# nestWidget.net
KiCad netlist of a schematic drawn in EAGLE
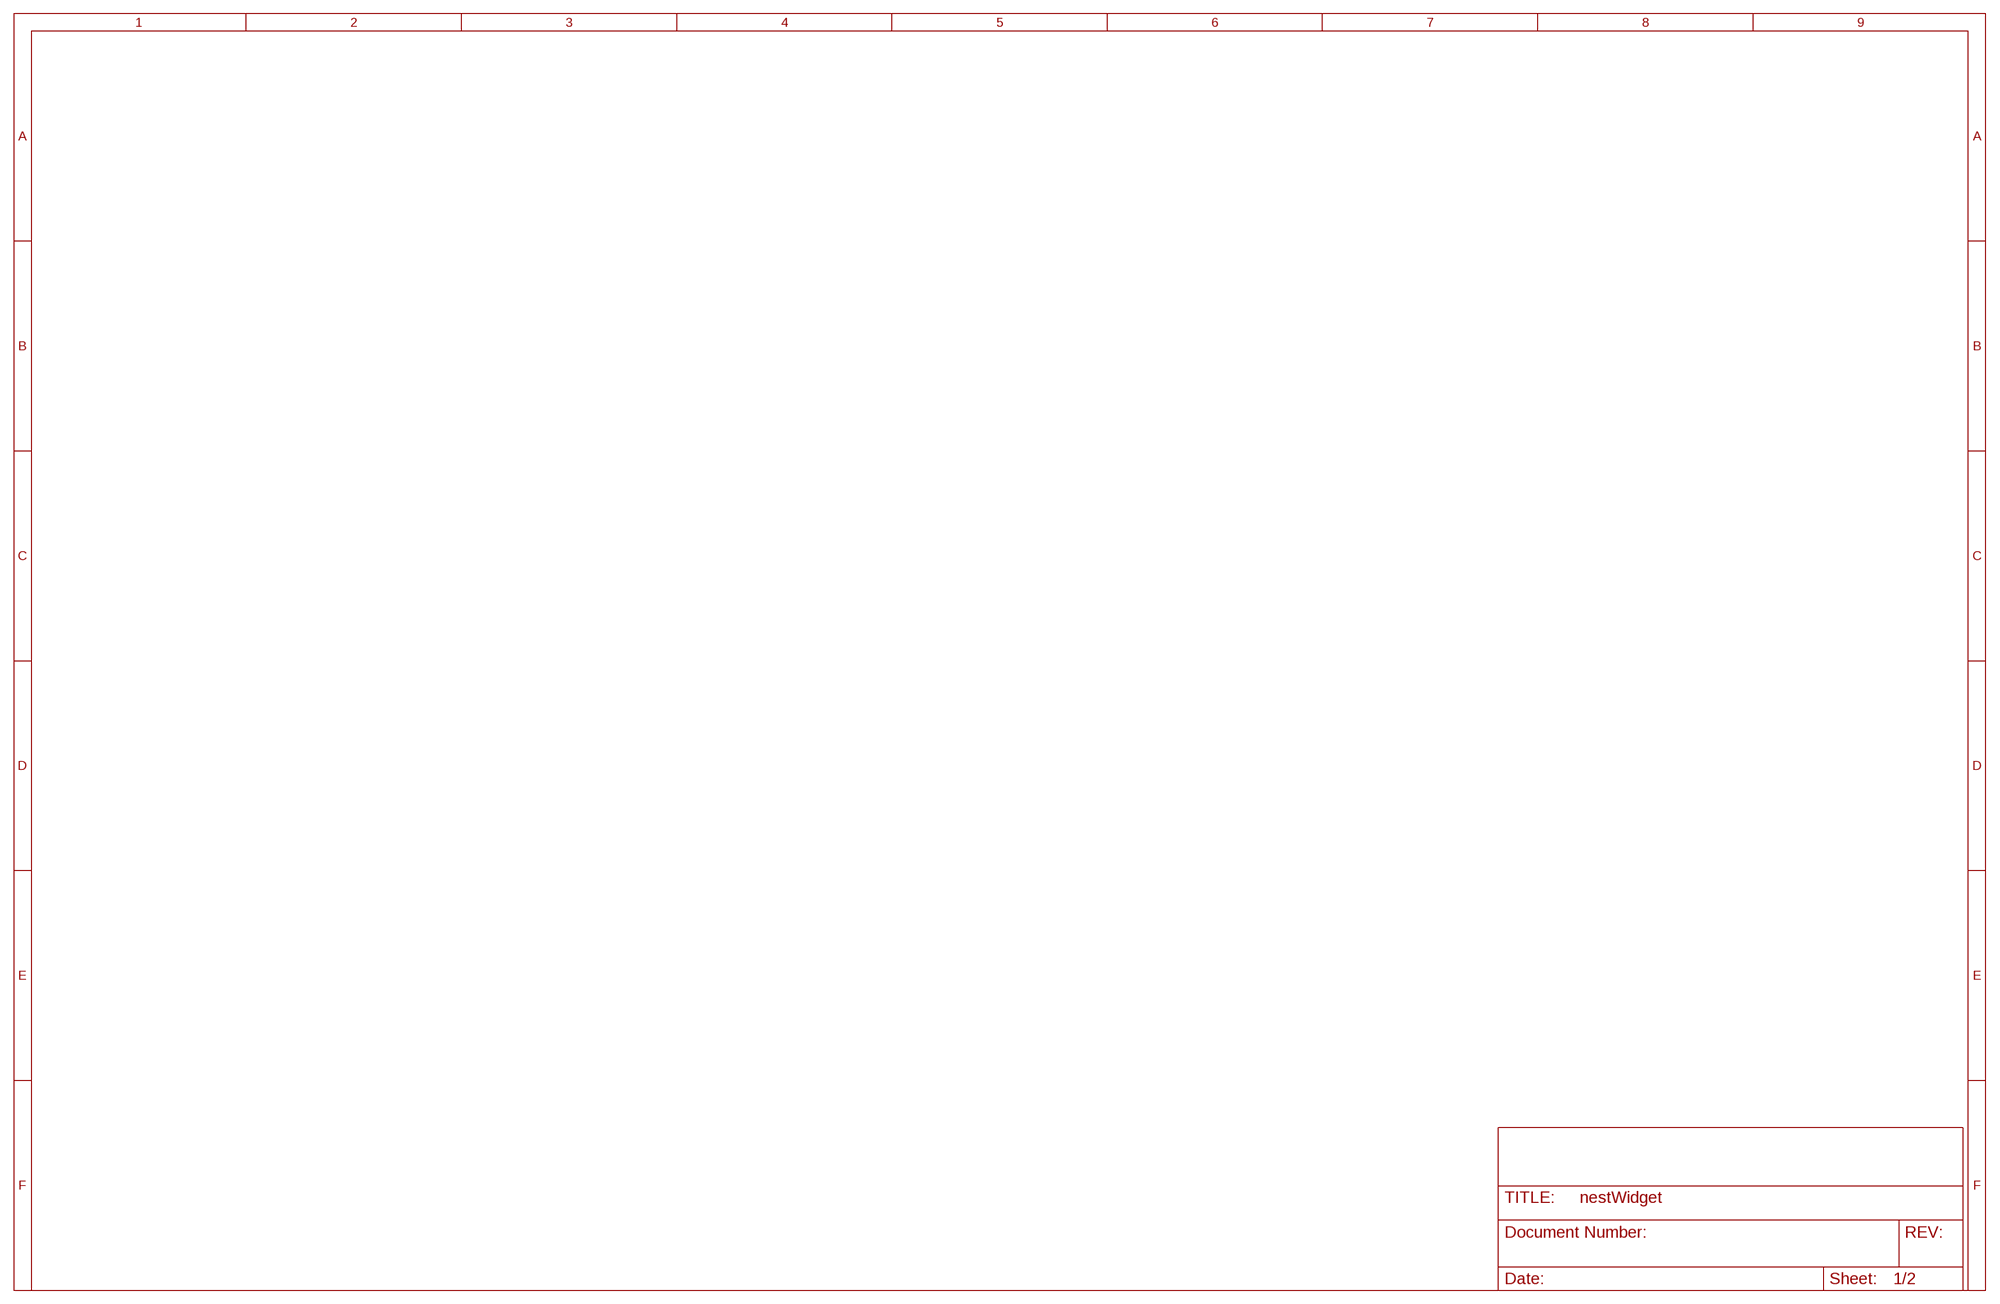
[diagram p0: schematic, sheet 1]
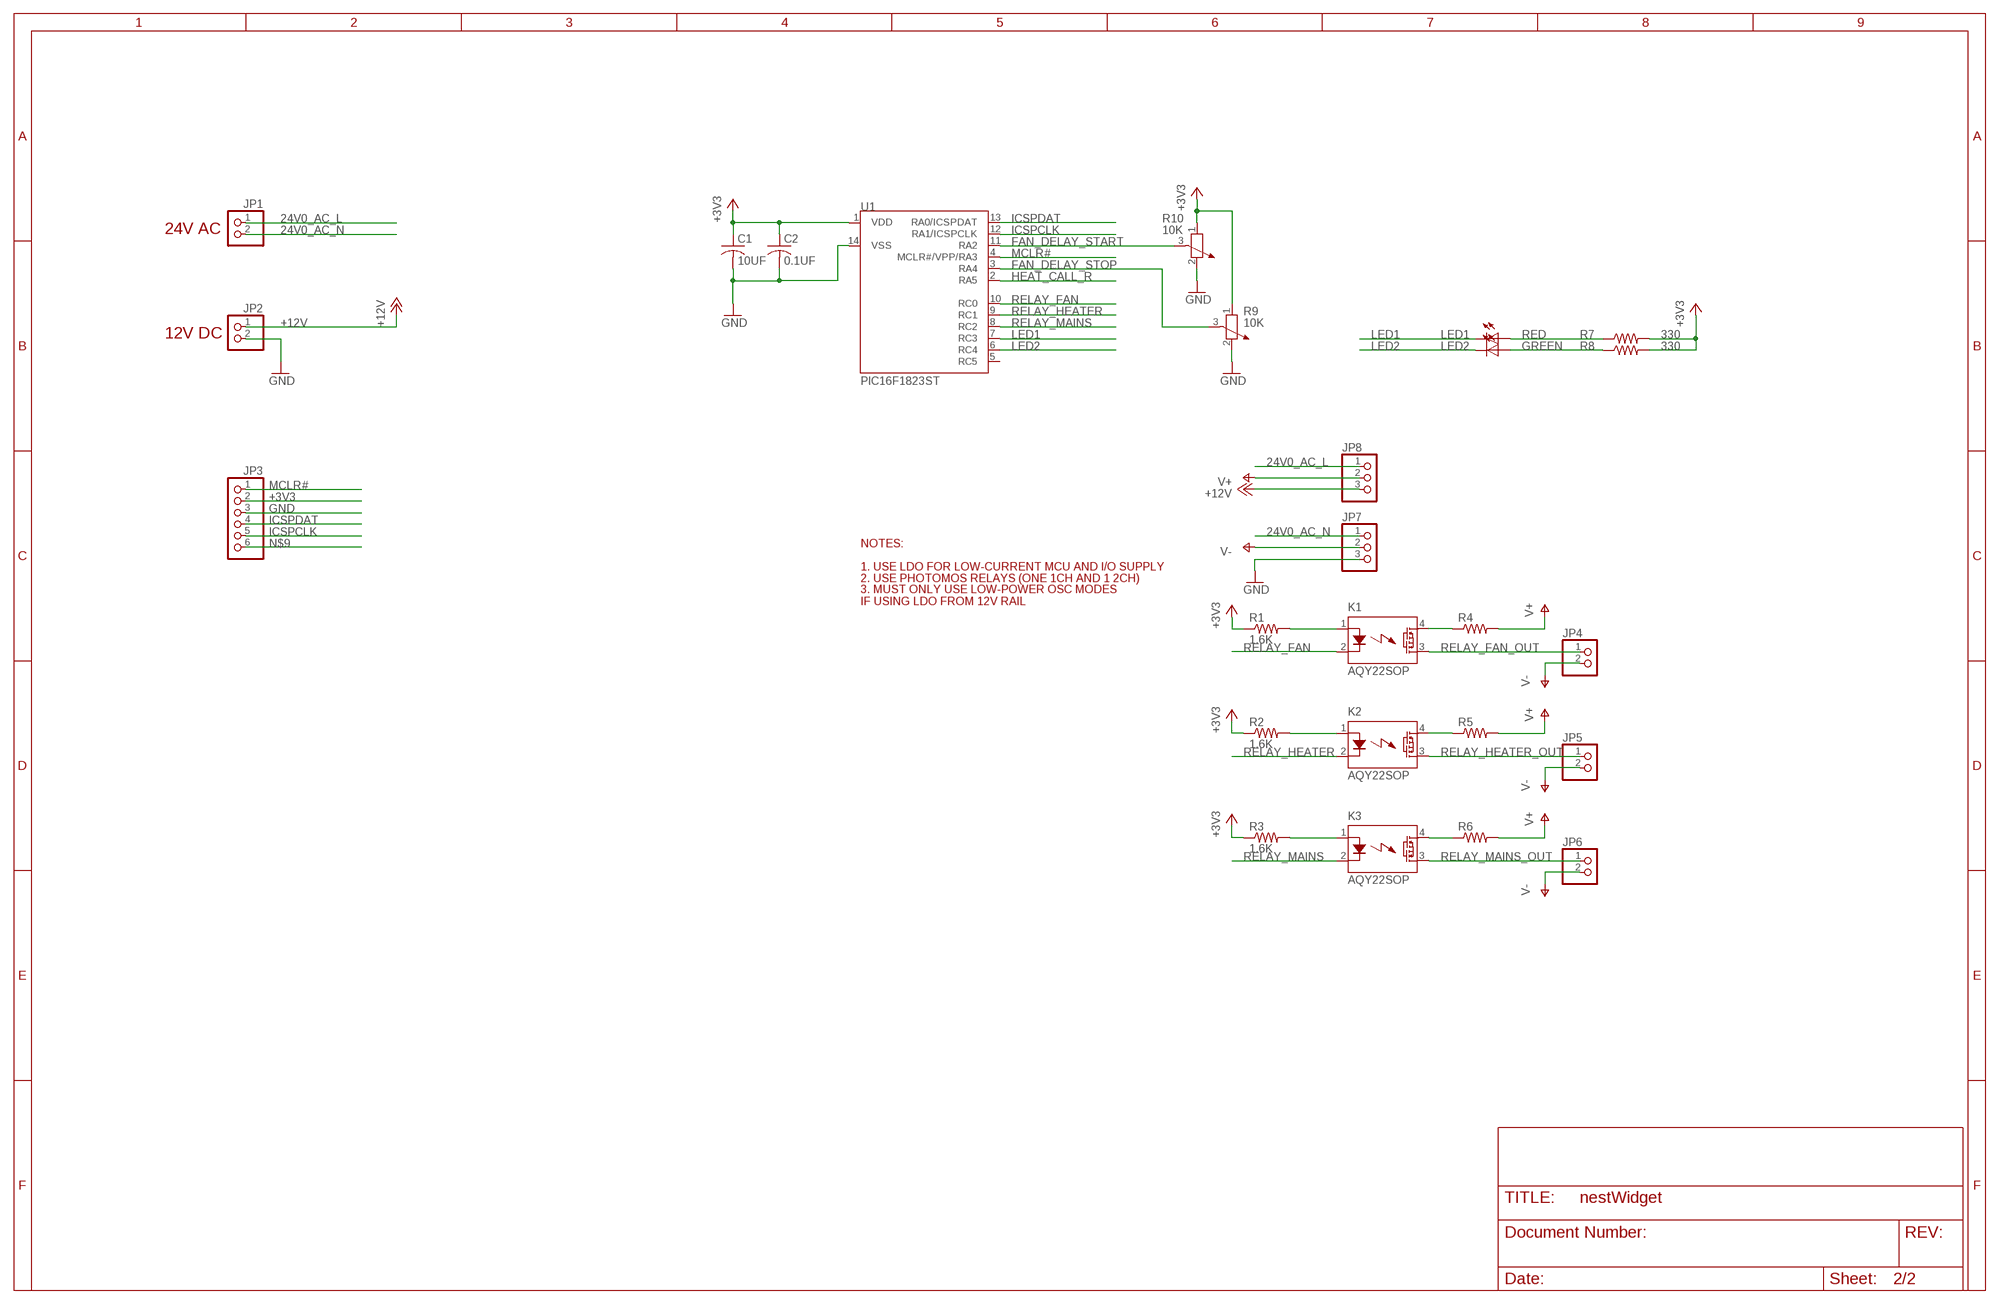
[diagram p1: schematic, sheet 2]

(export (version "E")
  (design (tool "Eeschema 10.0.6"))
  (components
    (comp (ref "C1")
      (value "10UF")
      (footprint "eagle-import:C0603")
      (libsource (lib "eagle-import") (part "C-USC0603"))
    )
    (comp (ref "C2")
      (value "0.1UF")
      (footprint "eagle-import:C0603")
      (libsource (lib "eagle-import") (part "C-USC0603"))
    )
    (comp (ref "JP1")
      (value "PINHD-1X2")
      (footprint "eagle-import:1X02")
      (libsource (lib "eagle-import") (part "PINHD-1X2"))
    )
    (comp (ref "JP2")
      (value "PINHD-1X2")
      (footprint "eagle-import:1X02")
      (libsource (lib "eagle-import") (part "PINHD-1X2"))
    )
    (comp (ref "JP3")
      (value "PINHD-1X6")
      (footprint "eagle-import:1X06")
      (libsource (lib "eagle-import") (part "PINHD-1X6"))
    )
    (comp (ref "JP4")
      (value "PINHD-1X2")
      (footprint "eagle-import:1X02")
      (libsource (lib "eagle-import") (part "PINHD-1X2"))
    )
    (comp (ref "JP5")
      (value "PINHD-1X2")
      (footprint "eagle-import:1X02")
      (libsource (lib "eagle-import") (part "PINHD-1X2"))
    )
    (comp (ref "JP6")
      (value "PINHD-1X2")
      (footprint "eagle-import:1X02")
      (libsource (lib "eagle-import") (part "PINHD-1X2"))
    )
    (comp (ref "JP7")
      (value "PINHD-1X3")
      (footprint "eagle-import:1X03")
      (libsource (lib "eagle-import") (part "PINHD-1X3"))
    )
    (comp (ref "JP8")
      (value "PINHD-1X3")
      (footprint "eagle-import:1X03")
      (libsource (lib "eagle-import") (part "PINHD-1X3"))
    )
    (comp (ref "K1")
      (value "AQY22SOP")
      (footprint "eagle-import:SOP04")
      (libsource (lib "eagle-import") (part "AQYSOP22"))
    )
    (comp (ref "K2")
      (value "AQY22SOP")
      (footprint "eagle-import:SOP04")
      (libsource (lib "eagle-import") (part "AQYSOP22"))
    )
    (comp (ref "K3")
      (value "AQY22SOP")
      (footprint "eagle-import:SOP04")
      (libsource (lib "eagle-import") (part "AQYSOP22"))
    )
    (comp (ref "LED1")
      (value "RED")
      (footprint "eagle-import:CHIPLED_0603")
      (libsource (lib "eagle-import") (part "LEDCHIPLED_0603"))
    )
    (comp (ref "LED2")
      (value "GREEN")
      (footprint "eagle-import:CHIPLED_0603")
      (libsource (lib "eagle-import") (part "LEDCHIPLED_0603"))
    )
    (comp (ref "R1")
      (value "1.6K")
      (footprint "eagle-import:R0603")
      (libsource (lib "eagle-import") (part "R-US_R0603"))
    )
    (comp (ref "R2")
      (value "1.6K")
      (footprint "eagle-import:R0603")
      (libsource (lib "eagle-import") (part "R-US_R0603"))
    )
    (comp (ref "R3")
      (value "1.6K")
      (footprint "eagle-import:R0603")
      (libsource (lib "eagle-import") (part "R-US_R0603"))
    )
    (comp (ref "R4")
      (value "R-US_R0603")
      (footprint "eagle-import:R0603")
      (libsource (lib "eagle-import") (part "R-US_R0603"))
    )
    (comp (ref "R5")
      (value "R-US_R0603")
      (footprint "eagle-import:R0603")
      (libsource (lib "eagle-import") (part "R-US_R0603"))
    )
    (comp (ref "R6")
      (value "R-US_R0603")
      (footprint "eagle-import:R0603")
      (libsource (lib "eagle-import") (part "R-US_R0603"))
    )
    (comp (ref "R7")
      (value "330")
      (footprint "eagle-import:R0603")
      (libsource (lib "eagle-import") (part "R-US_R0603"))
    )
    (comp (ref "R8")
      (value "330")
      (footprint "eagle-import:R0603")
      (libsource (lib "eagle-import") (part "R-US_R0603"))
    )
    (comp (ref "R9")
      (value "10K")
      (footprint "eagle-import:PT-10S")
      (libsource (lib "eagle-import") (part "POTENTIOMETER_PT-10S"))
    )
    (comp (ref "R10")
      (value "10K")
      (footprint "eagle-import:PT-10S")
      (libsource (lib "eagle-import") (part "POTENTIOMETER_PT-10S"))
    )
    (comp (ref "U1")
      (value "PIC16F1823ST")
      (footprint "eagle-import:TSSOP14")
      (libsource (lib "eagle-import") (part "PIC16F1823ST"))
    )
  )
  (nets
    (net (code "1") (name "+3V3") (class "Default")
      (node (ref "C1") (pin "1") (pinfunction "1_1") (pintype "passive"))
      (node (ref "C2") (pin "1") (pinfunction "1_1") (pintype "passive"))
      (node (ref "JP3") (pin "2") (pinfunction "2_2") (pintype "passive"))
      (node (ref "R1") (pin "1") (pinfunction "1_1") (pintype "passive"))
      (node (ref "R10") (pin "1") (pinfunction "1_1") (pintype "passive"))
      (node (ref "R2") (pin "1") (pinfunction "1_1") (pintype "passive"))
      (node (ref "R3") (pin "1") (pinfunction "1_1") (pintype "passive"))
      (node (ref "R7") (pin "2") (pinfunction "2_2") (pintype "passive"))
      (node (ref "R8") (pin "2") (pinfunction "2_2") (pintype "passive"))
      (node (ref "R9") (pin "1") (pinfunction "1_1") (pintype "passive"))
      (node (ref "U1") (pin "1") (pinfunction "VDD_1") (pintype "bidirectional"))
    )
    (net (code "2") (name "+12V") (class "Default")
      (node (ref "JP2") (pin "1") (pinfunction "1_1") (pintype "passive"))
      (node (ref "JP8") (pin "3") (pinfunction "3_3") (pintype "passive"))
    )
    (net (code "3") (name "24V0_AC_L") (class "Default")
      (node (ref "JP1") (pin "1") (pinfunction "1_1") (pintype "passive"))
      (node (ref "JP8") (pin "1") (pinfunction "1_1") (pintype "passive"))
    )
    (net (code "4") (name "24V0_AC_N") (class "Default")
      (node (ref "JP1") (pin "2") (pinfunction "2_2") (pintype "passive"))
      (node (ref "JP7") (pin "1") (pinfunction "1_1") (pintype "passive"))
    )
    (net (code "5") (name "FAN_DELAY_START") (class "Default")
      (node (ref "R10") (pin "3") (pinfunction "3_3") (pintype "passive"))
      (node (ref "U1") (pin "11") (pinfunction "RA2_11") (pintype "bidirectional"))
    )
    (net (code "6") (name "FAN_DELAY_STOP") (class "Default")
      (node (ref "R9") (pin "3") (pinfunction "3_3") (pintype "passive"))
      (node (ref "U1") (pin "3") (pinfunction "RA4_3") (pintype "bidirectional"))
    )
    (net (code "7") (name "GND") (class "Default")
      (node (ref "C1") (pin "2") (pinfunction "2_2") (pintype "passive"))
      (node (ref "C2") (pin "2") (pinfunction "2_2") (pintype "passive"))
      (node (ref "JP2") (pin "2") (pinfunction "2_2") (pintype "passive"))
      (node (ref "JP3") (pin "3") (pinfunction "3_3") (pintype "passive"))
      (node (ref "JP7") (pin "3") (pinfunction "3_3") (pintype "passive"))
      (node (ref "R10") (pin "2") (pinfunction "2_2") (pintype "passive"))
      (node (ref "R9") (pin "2") (pinfunction "2_2") (pintype "passive"))
      (node (ref "U1") (pin "14") (pinfunction "VSS_14") (pintype "bidirectional"))
    )
    (net (code "8") (name "HEAT_CALL_R") (class "Default")
      (node (ref "U1") (pin "2") (pinfunction "RA5_2") (pintype "bidirectional"))
    )
    (net (code "9") (name "ICSPCLK") (class "Default")
      (node (ref "JP3") (pin "5") (pinfunction "5_5") (pintype "passive"))
      (node (ref "U1") (pin "12") (pinfunction "RA1/ICSPCLK_12") (pintype "bidirectional"))
    )
    (net (code "10") (name "ICSPDAT") (class "Default")
      (node (ref "JP3") (pin "4") (pinfunction "4_4") (pintype "passive"))
      (node (ref "U1") (pin "13") (pinfunction "RA0/ICSPDAT_13") (pintype "bidirectional"))
    )
    (net (code "11") (name "LED1") (class "Default")
      (node (ref "LED1") (pin "C") (pinfunction "C_C") (pintype "passive"))
      (node (ref "U1") (pin "7") (pinfunction "RC3_7") (pintype "bidirectional"))
    )
    (net (code "12") (name "LED2") (class "Default")
      (node (ref "LED2") (pin "C") (pinfunction "C_C") (pintype "passive"))
      (node (ref "U1") (pin "6") (pinfunction "RC4_6") (pintype "bidirectional"))
    )
    (net (code "13") (name "MCLR#") (class "Default")
      (node (ref "JP3") (pin "1") (pinfunction "1_1") (pintype "passive"))
      (node (ref "U1") (pin "4") (pinfunction "MCLR#/VPP/RA3_4") (pintype "bidirectional"))
    )
    (net (code "14") (name "N$9") (class "Default")
      (node (ref "JP3") (pin "6") (pinfunction "6_6") (pintype "passive"))
    )
    (net (code "15") (name "Net-(K1-A)") (class "Default")
      (node (ref "K1") (pin "1") (pinfunction "A_1") (pintype "passive"))
      (node (ref "R1") (pin "2") (pinfunction "2_2") (pintype "passive"))
    )
    (net (code "16") (name "Net-(K1-DS1)") (class "Default")
      (node (ref "K1") (pin "4") (pinfunction "DS1_4") (pintype "passive"))
      (node (ref "R4") (pin "1") (pinfunction "1_1") (pintype "passive"))
    )
    (net (code "17") (name "Net-(K2-A)") (class "Default")
      (node (ref "K2") (pin "1") (pinfunction "A_1") (pintype "passive"))
      (node (ref "R2") (pin "2") (pinfunction "2_2") (pintype "passive"))
    )
    (net (code "18") (name "Net-(K2-DS1)") (class "Default")
      (node (ref "K2") (pin "4") (pinfunction "DS1_4") (pintype "passive"))
      (node (ref "R5") (pin "1") (pinfunction "1_1") (pintype "passive"))
    )
    (net (code "19") (name "Net-(K3-A)") (class "Default")
      (node (ref "K3") (pin "1") (pinfunction "A_1") (pintype "passive"))
      (node (ref "R3") (pin "2") (pinfunction "2_2") (pintype "passive"))
    )
    (net (code "20") (name "Net-(K3-DS1)") (class "Default")
      (node (ref "K3") (pin "4") (pinfunction "DS1_4") (pintype "passive"))
      (node (ref "R6") (pin "1") (pinfunction "1_1") (pintype "passive"))
    )
    (net (code "21") (name "Net-(LED1-PadA)") (class "Default")
      (node (ref "LED1") (pin "A") (pinfunction "A_A") (pintype "passive"))
      (node (ref "R7") (pin "1") (pinfunction "1_1") (pintype "passive"))
    )
    (net (code "22") (name "Net-(LED2-PadA)") (class "Default")
      (node (ref "LED2") (pin "A") (pinfunction "A_A") (pintype "passive"))
      (node (ref "R8") (pin "1") (pinfunction "1_1") (pintype "passive"))
    )
    (net (code "23") (name "RELAY_FAN") (class "Default")
      (node (ref "K1") (pin "2") (pinfunction "K_2") (pintype "passive"))
      (node (ref "U1") (pin "10") (pinfunction "RC0_10") (pintype "bidirectional"))
    )
    (net (code "24") (name "RELAY_FAN_OUT") (class "Default")
      (node (ref "JP4") (pin "1") (pinfunction "1_1") (pintype "passive"))
      (node (ref "K1") (pin "3") (pinfunction "DS2_3") (pintype "passive"))
    )
    (net (code "25") (name "RELAY_HEATER") (class "Default")
      (node (ref "K2") (pin "2") (pinfunction "K_2") (pintype "passive"))
      (node (ref "U1") (pin "9") (pinfunction "RC1_9") (pintype "bidirectional"))
    )
    (net (code "26") (name "RELAY_HEATER_OUT") (class "Default")
      (node (ref "JP5") (pin "1") (pinfunction "1_1") (pintype "passive"))
      (node (ref "K2") (pin "3") (pinfunction "DS2_3") (pintype "passive"))
    )
    (net (code "27") (name "RELAY_MAINS") (class "Default")
      (node (ref "K3") (pin "2") (pinfunction "K_2") (pintype "passive"))
      (node (ref "U1") (pin "8") (pinfunction "RC2_8") (pintype "bidirectional"))
    )
    (net (code "28") (name "RELAY_MAINS_OUT") (class "Default")
      (node (ref "JP6") (pin "1") (pinfunction "1_1") (pintype "passive"))
      (node (ref "K3") (pin "3") (pinfunction "DS2_3") (pintype "passive"))
    )
    (net (code "29") (name "V+") (class "Default")
      (node (ref "JP8") (pin "2") (pinfunction "2_2") (pintype "passive"))
      (node (ref "R4") (pin "2") (pinfunction "2_2") (pintype "passive"))
      (node (ref "R5") (pin "2") (pinfunction "2_2") (pintype "passive"))
      (node (ref "R6") (pin "2") (pinfunction "2_2") (pintype "passive"))
    )
    (net (code "30") (name "V-") (class "Default")
      (node (ref "JP4") (pin "2") (pinfunction "2_2") (pintype "passive"))
      (node (ref "JP5") (pin "2") (pinfunction "2_2") (pintype "passive"))
      (node (ref "JP6") (pin "2") (pinfunction "2_2") (pintype "passive"))
      (node (ref "JP7") (pin "2") (pinfunction "2_2") (pintype "passive"))
    )
    (net (code "31") (name "unconnected-(U1-RC5-Pad5)") (class "Default")
      (node (ref "U1") (pin "5") (pinfunction "RC5_5") (pintype "bidirectional"))
    )
  )
)
